# LC_BigOne_-_5_3A_MOSFET_for_TLC5940_2.net
KiCad netlist of a schematic drawn in Altium Designer
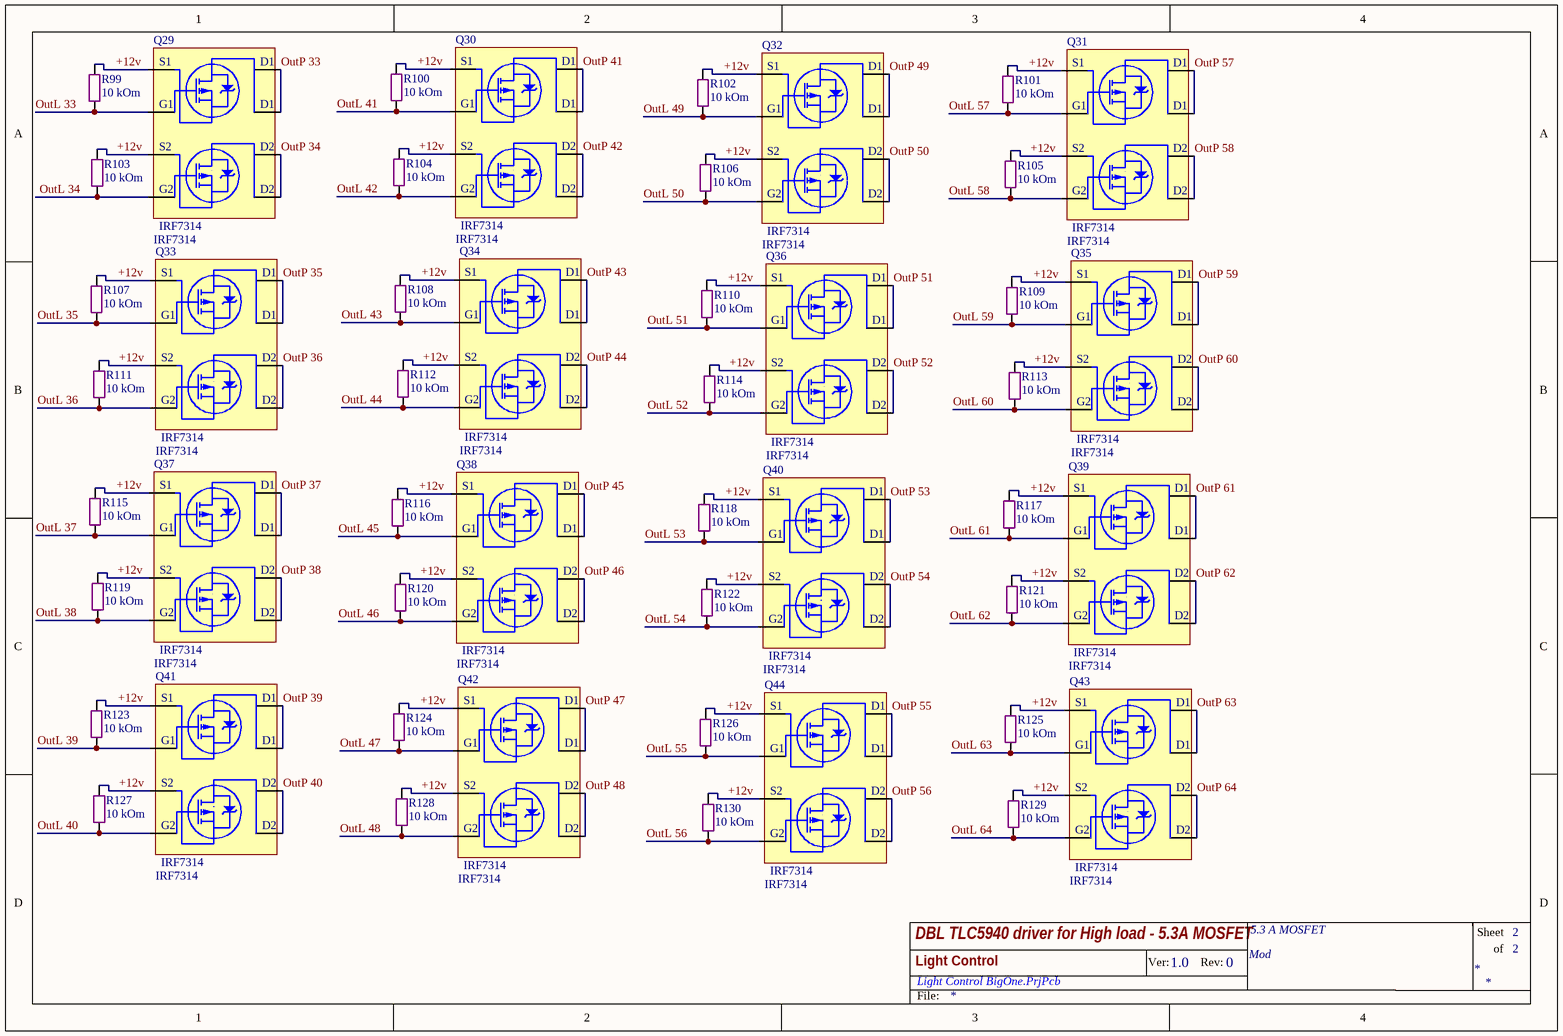
[diagram p0: LC BigOne - 5.3A MOSFET for TLC5940 2.SchDoc]

(export (version "E")
  (design (tool "Eeschema 10.0.6"))
  (components
    (comp (ref "Q29")
      (value "IRF7314")
      (footprint "GeneralCases:SO8")
      (description "Dual P-Ch  20V - 0.058Ω - 5.3A")
      (libsource (lib "Transistor") (part "IRF7314"))
    )
    (comp (ref "Q30")
      (value "IRF7314")
      (footprint "GeneralCases:SO8")
      (description "Dual P-Ch  20V - 0.058Ω - 5.3A")
      (libsource (lib "Transistor") (part "IRF7314"))
    )
    (comp (ref "Q31")
      (value "IRF7314")
      (footprint "GeneralCases:SO8")
      (description "Dual P-Ch  20V - 0.058Ω - 5.3A")
      (libsource (lib "Transistor") (part "IRF7314"))
    )
    (comp (ref "Q32")
      (value "IRF7314")
      (footprint "GeneralCases:SO8")
      (description "Dual P-Ch  20V - 0.058Ω - 5.3A")
      (libsource (lib "Transistor") (part "IRF7314"))
    )
    (comp (ref "Q33")
      (value "IRF7314")
      (footprint "GeneralCases:SO8")
      (description "Dual P-Ch  20V - 0.058Ω - 5.3A")
      (libsource (lib "Transistor") (part "IRF7314"))
    )
    (comp (ref "Q34")
      (value "IRF7314")
      (footprint "GeneralCases:SO8")
      (description "Dual P-Ch  20V - 0.058Ω - 5.3A")
      (libsource (lib "Transistor") (part "IRF7314"))
    )
    (comp (ref "Q35")
      (value "IRF7314")
      (footprint "GeneralCases:SO8")
      (description "Dual P-Ch  20V - 0.058Ω - 5.3A")
      (libsource (lib "Transistor") (part "IRF7314"))
    )
    (comp (ref "Q36")
      (value "IRF7314")
      (footprint "GeneralCases:SO8")
      (description "Dual P-Ch  20V - 0.058Ω - 5.3A")
      (libsource (lib "Transistor") (part "IRF7314"))
    )
    (comp (ref "Q37")
      (value "IRF7314")
      (footprint "GeneralCases:SO8")
      (description "Dual P-Ch  20V - 0.058Ω - 5.3A")
      (libsource (lib "Transistor") (part "IRF7314"))
    )
    (comp (ref "Q38")
      (value "IRF7314")
      (footprint "GeneralCases:SO8")
      (description "Dual P-Ch  20V - 0.058Ω - 5.3A")
      (libsource (lib "Transistor") (part "IRF7314"))
    )
    (comp (ref "Q39")
      (value "IRF7314")
      (footprint "GeneralCases:SO8")
      (description "Dual P-Ch  20V - 0.058Ω - 5.3A")
      (libsource (lib "Transistor") (part "IRF7314"))
    )
    (comp (ref "Q40")
      (value "IRF7314")
      (footprint "GeneralCases:SO8")
      (description "Dual P-Ch  20V - 0.058Ω - 5.3A")
      (libsource (lib "Transistor") (part "IRF7314"))
    )
    (comp (ref "Q41")
      (value "IRF7314")
      (footprint "GeneralCases:SO8")
      (description "Dual P-Ch  20V - 0.058Ω - 5.3A")
      (libsource (lib "Transistor") (part "IRF7314"))
    )
    (comp (ref "Q42")
      (value "IRF7314")
      (footprint "GeneralCases:SO8")
      (description "Dual P-Ch  20V - 0.058Ω - 5.3A")
      (libsource (lib "Transistor") (part "IRF7314"))
    )
    (comp (ref "Q43")
      (value "IRF7314")
      (footprint "GeneralCases:SO8")
      (description "Dual P-Ch  20V - 0.058Ω - 5.3A")
      (libsource (lib "Transistor") (part "IRF7314"))
    )
    (comp (ref "Q44")
      (value "IRF7314")
      (footprint "GeneralCases:SO8")
      (description "Dual P-Ch  20V - 0.058Ω - 5.3A")
      (libsource (lib "Transistor") (part "IRF7314"))
    )
    (comp (ref "R99")
      (value "10 kOm")
      (footprint "PassiveComponents:SMD 0805 (2012)")
      (libsource (lib "PassiveComponents") (part "Res All Types"))
    )
    (comp (ref "R100")
      (value "10 kOm")
      (footprint "PassiveComponents:SMD 0805 (2012)")
      (libsource (lib "PassiveComponents") (part "Res All Types"))
    )
    (comp (ref "R101")
      (value "10 kOm")
      (footprint "PassiveComponents:SMD 0805 (2012)")
      (libsource (lib "PassiveComponents") (part "Res All Types"))
    )
    (comp (ref "R102")
      (value "10 kOm")
      (footprint "PassiveComponents:SMD 0805 (2012)")
      (libsource (lib "PassiveComponents") (part "Res All Types"))
    )
    (comp (ref "R103")
      (value "10 kOm")
      (footprint "PassiveComponents:SMD 0805 (2012)")
      (libsource (lib "PassiveComponents") (part "Res All Types"))
    )
    (comp (ref "R104")
      (value "10 kOm")
      (footprint "PassiveComponents:SMD 0805 (2012)")
      (libsource (lib "PassiveComponents") (part "Res All Types"))
    )
    (comp (ref "R105")
      (value "10 kOm")
      (footprint "PassiveComponents:SMD 0805 (2012)")
      (libsource (lib "PassiveComponents") (part "Res All Types"))
    )
    (comp (ref "R106")
      (value "10 kOm")
      (footprint "PassiveComponents:SMD 0805 (2012)")
      (libsource (lib "PassiveComponents") (part "Res All Types"))
    )
    (comp (ref "R107")
      (value "10 kOm")
      (footprint "PassiveComponents:SMD 0805 (2012)")
      (libsource (lib "PassiveComponents") (part "Res All Types"))
    )
    (comp (ref "R108")
      (value "10 kOm")
      (footprint "PassiveComponents:SMD 0805 (2012)")
      (libsource (lib "PassiveComponents") (part "Res All Types"))
    )
    (comp (ref "R109")
      (value "10 kOm")
      (footprint "PassiveComponents:SMD 0805 (2012)")
      (libsource (lib "PassiveComponents") (part "Res All Types"))
    )
    (comp (ref "R110")
      (value "10 kOm")
      (footprint "PassiveComponents:SMD 0805 (2012)")
      (libsource (lib "PassiveComponents") (part "Res All Types"))
    )
    (comp (ref "R111")
      (value "10 kOm")
      (footprint "PassiveComponents:SMD 0805 (2012)")
      (libsource (lib "PassiveComponents") (part "Res All Types"))
    )
    (comp (ref "R112")
      (value "10 kOm")
      (footprint "PassiveComponents:SMD 0805 (2012)")
      (libsource (lib "PassiveComponents") (part "Res All Types"))
    )
    (comp (ref "R113")
      (value "10 kOm")
      (footprint "PassiveComponents:SMD 0805 (2012)")
      (libsource (lib "PassiveComponents") (part "Res All Types"))
    )
    (comp (ref "R114")
      (value "10 kOm")
      (footprint "PassiveComponents:SMD 0805 (2012)")
      (libsource (lib "PassiveComponents") (part "Res All Types"))
    )
    (comp (ref "R115")
      (value "10 kOm")
      (footprint "PassiveComponents:SMD 0805 (2012)")
      (libsource (lib "PassiveComponents") (part "Res All Types"))
    )
    (comp (ref "R116")
      (value "10 kOm")
      (footprint "PassiveComponents:SMD 0805 (2012)")
      (libsource (lib "PassiveComponents") (part "Res All Types"))
    )
    (comp (ref "R117")
      (value "10 kOm")
      (footprint "PassiveComponents:SMD 0805 (2012)")
      (libsource (lib "PassiveComponents") (part "Res All Types"))
    )
    (comp (ref "R118")
      (value "10 kOm")
      (footprint "PassiveComponents:SMD 0805 (2012)")
      (libsource (lib "PassiveComponents") (part "Res All Types"))
    )
    (comp (ref "R119")
      (value "10 kOm")
      (footprint "PassiveComponents:SMD 0805 (2012)")
      (libsource (lib "PassiveComponents") (part "Res All Types"))
    )
    (comp (ref "R120")
      (value "10 kOm")
      (footprint "PassiveComponents:SMD 0805 (2012)")
      (libsource (lib "PassiveComponents") (part "Res All Types"))
    )
    (comp (ref "R121")
      (value "10 kOm")
      (footprint "PassiveComponents:SMD 0805 (2012)")
      (libsource (lib "PassiveComponents") (part "Res All Types"))
    )
    (comp (ref "R122")
      (value "10 kOm")
      (footprint "PassiveComponents:SMD 0805 (2012)")
      (libsource (lib "PassiveComponents") (part "Res All Types"))
    )
    (comp (ref "R123")
      (value "10 kOm")
      (footprint "PassiveComponents:SMD 0805 (2012)")
      (libsource (lib "PassiveComponents") (part "Res All Types"))
    )
    (comp (ref "R124")
      (value "10 kOm")
      (footprint "PassiveComponents:SMD 0805 (2012)")
      (libsource (lib "PassiveComponents") (part "Res All Types"))
    )
    (comp (ref "R125")
      (value "10 kOm")
      (footprint "PassiveComponents:SMD 0805 (2012)")
      (libsource (lib "PassiveComponents") (part "Res All Types"))
    )
    (comp (ref "R126")
      (value "10 kOm")
      (footprint "PassiveComponents:SMD 0805 (2012)")
      (libsource (lib "PassiveComponents") (part "Res All Types"))
    )
    (comp (ref "R127")
      (value "10 kOm")
      (footprint "PassiveComponents:SMD 0805 (2012)")
      (libsource (lib "PassiveComponents") (part "Res All Types"))
    )
    (comp (ref "R128")
      (value "10 kOm")
      (footprint "PassiveComponents:SMD 0805 (2012)")
      (libsource (lib "PassiveComponents") (part "Res All Types"))
    )
    (comp (ref "R129")
      (value "10 kOm")
      (footprint "PassiveComponents:SMD 0805 (2012)")
      (libsource (lib "PassiveComponents") (part "Res All Types"))
    )
    (comp (ref "R130")
      (value "10 kOm")
      (footprint "PassiveComponents:SMD 0805 (2012)")
      (libsource (lib "PassiveComponents") (part "Res All Types"))
    )
  )
  (nets
    (net (code "1") (name "/+12v") (class "Default")
      (node (ref "Q29") (pin "1") (pinfunction "S_1") (pintype "passive"))
      (node (ref "Q29") (pin "3") (pinfunction "S_3") (pintype "passive"))
      (node (ref "Q30") (pin "1") (pinfunction "S_1") (pintype "passive"))
      (node (ref "Q30") (pin "3") (pinfunction "S_3") (pintype "passive"))
      (node (ref "Q31") (pin "1") (pinfunction "S_1") (pintype "passive"))
      (node (ref "Q31") (pin "3") (pinfunction "S_3") (pintype "passive"))
      (node (ref "Q32") (pin "1") (pinfunction "S_1") (pintype "passive"))
      (node (ref "Q32") (pin "3") (pinfunction "S_3") (pintype "passive"))
      (node (ref "Q33") (pin "1") (pinfunction "S_1") (pintype "passive"))
      (node (ref "Q33") (pin "3") (pinfunction "S_3") (pintype "passive"))
      (node (ref "Q34") (pin "1") (pinfunction "S_1") (pintype "passive"))
      (node (ref "Q34") (pin "3") (pinfunction "S_3") (pintype "passive"))
      (node (ref "Q35") (pin "1") (pinfunction "S_1") (pintype "passive"))
      (node (ref "Q35") (pin "3") (pinfunction "S_3") (pintype "passive"))
      (node (ref "Q36") (pin "1") (pinfunction "S_1") (pintype "passive"))
      (node (ref "Q36") (pin "3") (pinfunction "S_3") (pintype "passive"))
      (node (ref "Q37") (pin "1") (pinfunction "S_1") (pintype "passive"))
      (node (ref "Q37") (pin "3") (pinfunction "S_3") (pintype "passive"))
      (node (ref "Q38") (pin "1") (pinfunction "S_1") (pintype "passive"))
      (node (ref "Q38") (pin "3") (pinfunction "S_3") (pintype "passive"))
      (node (ref "Q39") (pin "1") (pinfunction "S_1") (pintype "passive"))
      (node (ref "Q39") (pin "3") (pinfunction "S_3") (pintype "passive"))
      (node (ref "Q40") (pin "1") (pinfunction "S_1") (pintype "passive"))
      (node (ref "Q40") (pin "3") (pinfunction "S_3") (pintype "passive"))
      (node (ref "Q41") (pin "1") (pinfunction "S_1") (pintype "passive"))
      (node (ref "Q41") (pin "3") (pinfunction "S_3") (pintype "passive"))
      (node (ref "Q42") (pin "1") (pinfunction "S_1") (pintype "passive"))
      (node (ref "Q42") (pin "3") (pinfunction "S_3") (pintype "passive"))
      (node (ref "Q43") (pin "1") (pinfunction "S_1") (pintype "passive"))
      (node (ref "Q43") (pin "3") (pinfunction "S_3") (pintype "passive"))
      (node (ref "Q44") (pin "1") (pinfunction "S_1") (pintype "passive"))
      (node (ref "Q44") (pin "3") (pinfunction "S_3") (pintype "passive"))
      (node (ref "R100") (pin "2") (pinfunction "2_2") (pintype "passive"))
      (node (ref "R101") (pin "2") (pinfunction "2_2") (pintype "passive"))
      (node (ref "R102") (pin "2") (pinfunction "2_2") (pintype "passive"))
      (node (ref "R103") (pin "2") (pinfunction "2_2") (pintype "passive"))
      (node (ref "R104") (pin "2") (pinfunction "2_2") (pintype "passive"))
      (node (ref "R105") (pin "2") (pinfunction "2_2") (pintype "passive"))
      (node (ref "R106") (pin "2") (pinfunction "2_2") (pintype "passive"))
      (node (ref "R107") (pin "2") (pinfunction "2_2") (pintype "passive"))
      (node (ref "R108") (pin "2") (pinfunction "2_2") (pintype "passive"))
      (node (ref "R109") (pin "2") (pinfunction "2_2") (pintype "passive"))
      (node (ref "R110") (pin "2") (pinfunction "2_2") (pintype "passive"))
      (node (ref "R111") (pin "2") (pinfunction "2_2") (pintype "passive"))
      (node (ref "R112") (pin "2") (pinfunction "2_2") (pintype "passive"))
      (node (ref "R113") (pin "2") (pinfunction "2_2") (pintype "passive"))
      (node (ref "R114") (pin "2") (pinfunction "2_2") (pintype "passive"))
      (node (ref "R115") (pin "2") (pinfunction "2_2") (pintype "passive"))
      (node (ref "R116") (pin "2") (pinfunction "2_2") (pintype "passive"))
      (node (ref "R117") (pin "2") (pinfunction "2_2") (pintype "passive"))
      (node (ref "R118") (pin "2") (pinfunction "2_2") (pintype "passive"))
      (node (ref "R119") (pin "2") (pinfunction "2_2") (pintype "passive"))
      (node (ref "R120") (pin "2") (pinfunction "2_2") (pintype "passive"))
      (node (ref "R121") (pin "2") (pinfunction "2_2") (pintype "passive"))
      (node (ref "R122") (pin "2") (pinfunction "2_2") (pintype "passive"))
      (node (ref "R123") (pin "2") (pinfunction "2_2") (pintype "passive"))
      (node (ref "R124") (pin "2") (pinfunction "2_2") (pintype "passive"))
      (node (ref "R125") (pin "2") (pinfunction "2_2") (pintype "passive"))
      (node (ref "R126") (pin "2") (pinfunction "2_2") (pintype "passive"))
      (node (ref "R127") (pin "2") (pinfunction "2_2") (pintype "passive"))
      (node (ref "R128") (pin "2") (pinfunction "2_2") (pintype "passive"))
      (node (ref "R129") (pin "2") (pinfunction "2_2") (pintype "passive"))
      (node (ref "R130") (pin "2") (pinfunction "2_2") (pintype "passive"))
      (node (ref "R99") (pin "2") (pinfunction "2_2") (pintype "passive"))
    )
    (net (code "2") (name "/OutL 33") (class "Default")
      (node (ref "Q29") (pin "2") (pinfunction "G_2") (pintype "passive"))
      (node (ref "R99") (pin "1") (pinfunction "1_1") (pintype "passive"))
    )
    (net (code "3") (name "/OutL 34") (class "Default")
      (node (ref "Q29") (pin "4") (pinfunction "G_4") (pintype "passive"))
      (node (ref "R103") (pin "1") (pinfunction "1_1") (pintype "passive"))
    )
    (net (code "4") (name "/OutL 35") (class "Default")
      (node (ref "Q33") (pin "2") (pinfunction "G_2") (pintype "passive"))
      (node (ref "R107") (pin "1") (pinfunction "1_1") (pintype "passive"))
    )
    (net (code "5") (name "/OutL 36") (class "Default")
      (node (ref "Q33") (pin "4") (pinfunction "G_4") (pintype "passive"))
      (node (ref "R111") (pin "1") (pinfunction "1_1") (pintype "passive"))
    )
    (net (code "6") (name "/OutL 37") (class "Default")
      (node (ref "Q37") (pin "2") (pinfunction "G_2") (pintype "passive"))
      (node (ref "R115") (pin "1") (pinfunction "1_1") (pintype "passive"))
    )
    (net (code "7") (name "/OutL 38") (class "Default")
      (node (ref "Q37") (pin "4") (pinfunction "G_4") (pintype "passive"))
      (node (ref "R119") (pin "1") (pinfunction "1_1") (pintype "passive"))
    )
    (net (code "8") (name "/OutL 39") (class "Default")
      (node (ref "Q41") (pin "2") (pinfunction "G_2") (pintype "passive"))
      (node (ref "R123") (pin "1") (pinfunction "1_1") (pintype "passive"))
    )
    (net (code "9") (name "/OutL 40") (class "Default")
      (node (ref "Q41") (pin "4") (pinfunction "G_4") (pintype "passive"))
      (node (ref "R127") (pin "1") (pinfunction "1_1") (pintype "passive"))
    )
    (net (code "10") (name "/OutL 41") (class "Default")
      (node (ref "Q30") (pin "2") (pinfunction "G_2") (pintype "passive"))
      (node (ref "R100") (pin "1") (pinfunction "1_1") (pintype "passive"))
    )
    (net (code "11") (name "/OutL 42") (class "Default")
      (node (ref "Q30") (pin "4") (pinfunction "G_4") (pintype "passive"))
      (node (ref "R104") (pin "1") (pinfunction "1_1") (pintype "passive"))
    )
    (net (code "12") (name "/OutL 43") (class "Default")
      (node (ref "Q34") (pin "2") (pinfunction "G_2") (pintype "passive"))
      (node (ref "R108") (pin "1") (pinfunction "1_1") (pintype "passive"))
    )
    (net (code "13") (name "/OutL 44") (class "Default")
      (node (ref "Q34") (pin "4") (pinfunction "G_4") (pintype "passive"))
      (node (ref "R112") (pin "1") (pinfunction "1_1") (pintype "passive"))
    )
    (net (code "14") (name "/OutL 45") (class "Default")
      (node (ref "Q38") (pin "2") (pinfunction "G_2") (pintype "passive"))
      (node (ref "R116") (pin "1") (pinfunction "1_1") (pintype "passive"))
    )
    (net (code "15") (name "/OutL 46") (class "Default")
      (node (ref "Q38") (pin "4") (pinfunction "G_4") (pintype "passive"))
      (node (ref "R120") (pin "1") (pinfunction "1_1") (pintype "passive"))
    )
    (net (code "16") (name "/OutL 47") (class "Default")
      (node (ref "Q42") (pin "2") (pinfunction "G_2") (pintype "passive"))
      (node (ref "R124") (pin "1") (pinfunction "1_1") (pintype "passive"))
    )
    (net (code "17") (name "/OutL 48") (class "Default")
      (node (ref "Q42") (pin "4") (pinfunction "G_4") (pintype "passive"))
      (node (ref "R128") (pin "1") (pinfunction "1_1") (pintype "passive"))
    )
    (net (code "18") (name "/OutL 49") (class "Default")
      (node (ref "Q32") (pin "2") (pinfunction "G_2") (pintype "passive"))
      (node (ref "R102") (pin "1") (pinfunction "1_1") (pintype "passive"))
    )
    (net (code "19") (name "/OutL 50") (class "Default")
      (node (ref "Q32") (pin "4") (pinfunction "G_4") (pintype "passive"))
      (node (ref "R106") (pin "1") (pinfunction "1_1") (pintype "passive"))
    )
    (net (code "20") (name "/OutL 51") (class "Default")
      (node (ref "Q36") (pin "2") (pinfunction "G_2") (pintype "passive"))
      (node (ref "R110") (pin "1") (pinfunction "1_1") (pintype "passive"))
    )
    (net (code "21") (name "/OutL 52") (class "Default")
      (node (ref "Q36") (pin "4") (pinfunction "G_4") (pintype "passive"))
      (node (ref "R114") (pin "1") (pinfunction "1_1") (pintype "passive"))
    )
    (net (code "22") (name "/OutL 53") (class "Default")
      (node (ref "Q40") (pin "2") (pinfunction "G_2") (pintype "passive"))
      (node (ref "R118") (pin "1") (pinfunction "1_1") (pintype "passive"))
    )
    (net (code "23") (name "/OutL 54") (class "Default")
      (node (ref "Q40") (pin "4") (pinfunction "G_4") (pintype "passive"))
      (node (ref "R122") (pin "1") (pinfunction "1_1") (pintype "passive"))
    )
    (net (code "24") (name "/OutL 55") (class "Default")
      (node (ref "Q44") (pin "2") (pinfunction "G_2") (pintype "passive"))
      (node (ref "R126") (pin "1") (pinfunction "1_1") (pintype "passive"))
    )
    (net (code "25") (name "/OutL 56") (class "Default")
      (node (ref "Q44") (pin "4") (pinfunction "G_4") (pintype "passive"))
      (node (ref "R130") (pin "1") (pinfunction "1_1") (pintype "passive"))
    )
    (net (code "26") (name "/OutL 57") (class "Default")
      (node (ref "Q31") (pin "2") (pinfunction "G_2") (pintype "passive"))
      (node (ref "R101") (pin "1") (pinfunction "1_1") (pintype "passive"))
    )
    (net (code "27") (name "/OutL 58") (class "Default")
      (node (ref "Q31") (pin "4") (pinfunction "G_4") (pintype "passive"))
      (node (ref "R105") (pin "1") (pinfunction "1_1") (pintype "passive"))
    )
    (net (code "28") (name "/OutL 59") (class "Default")
      (node (ref "Q35") (pin "2") (pinfunction "G_2") (pintype "passive"))
      (node (ref "R109") (pin "1") (pinfunction "1_1") (pintype "passive"))
    )
    (net (code "29") (name "/OutL 60") (class "Default")
      (node (ref "Q35") (pin "4") (pinfunction "G_4") (pintype "passive"))
      (node (ref "R113") (pin "1") (pinfunction "1_1") (pintype "passive"))
    )
    (net (code "30") (name "/OutL 61") (class "Default")
      (node (ref "Q39") (pin "2") (pinfunction "G_2") (pintype "passive"))
      (node (ref "R117") (pin "1") (pinfunction "1_1") (pintype "passive"))
    )
    (net (code "31") (name "/OutL 62") (class "Default")
      (node (ref "Q39") (pin "4") (pinfunction "G_4") (pintype "passive"))
      (node (ref "R121") (pin "1") (pinfunction "1_1") (pintype "passive"))
    )
    (net (code "32") (name "/OutL 63") (class "Default")
      (node (ref "Q43") (pin "2") (pinfunction "G_2") (pintype "passive"))
      (node (ref "R125") (pin "1") (pinfunction "1_1") (pintype "passive"))
    )
    (net (code "33") (name "/OutL 64") (class "Default")
      (node (ref "Q43") (pin "4") (pinfunction "G_4") (pintype "passive"))
      (node (ref "R129") (pin "1") (pinfunction "1_1") (pintype "passive"))
    )
    (net (code "34") (name "/OutP 33") (class "Default")
      (node (ref "Q29") (pin "7") (pinfunction "D_7") (pintype "passive"))
      (node (ref "Q29") (pin "8") (pinfunction "D_8") (pintype "passive"))
    )
    (net (code "35") (name "/OutP 34") (class "Default")
      (node (ref "Q29") (pin "5") (pinfunction "D_5") (pintype "passive"))
      (node (ref "Q29") (pin "6") (pinfunction "D_6") (pintype "passive"))
    )
    (net (code "36") (name "/OutP 35") (class "Default")
      (node (ref "Q33") (pin "7") (pinfunction "D_7") (pintype "passive"))
      (node (ref "Q33") (pin "8") (pinfunction "D_8") (pintype "passive"))
    )
    (net (code "37") (name "/OutP 36") (class "Default")
      (node (ref "Q33") (pin "5") (pinfunction "D_5") (pintype "passive"))
      (node (ref "Q33") (pin "6") (pinfunction "D_6") (pintype "passive"))
    )
    (net (code "38") (name "/OutP 37") (class "Default")
      (node (ref "Q37") (pin "7") (pinfunction "D_7") (pintype "passive"))
      (node (ref "Q37") (pin "8") (pinfunction "D_8") (pintype "passive"))
    )
    (net (code "39") (name "/OutP 38") (class "Default")
      (node (ref "Q37") (pin "5") (pinfunction "D_5") (pintype "passive"))
      (node (ref "Q37") (pin "6") (pinfunction "D_6") (pintype "passive"))
    )
    (net (code "40") (name "/OutP 39") (class "Default")
      (node (ref "Q41") (pin "7") (pinfunction "D_7") (pintype "passive"))
      (node (ref "Q41") (pin "8") (pinfunction "D_8") (pintype "passive"))
    )
    (net (code "41") (name "/OutP 40") (class "Default")
      (node (ref "Q41") (pin "5") (pinfunction "D_5") (pintype "passive"))
      (node (ref "Q41") (pin "6") (pinfunction "D_6") (pintype "passive"))
    )
    (net (code "42") (name "/OutP 41") (class "Default")
      (node (ref "Q30") (pin "7") (pinfunction "D_7") (pintype "passive"))
      (node (ref "Q30") (pin "8") (pinfunction "D_8") (pintype "passive"))
    )
    (net (code "43") (name "/OutP 42") (class "Default")
      (node (ref "Q30") (pin "5") (pinfunction "D_5") (pintype "passive"))
      (node (ref "Q30") (pin "6") (pinfunction "D_6") (pintype "passive"))
    )
    (net (code "44") (name "/OutP 43") (class "Default")
      (node (ref "Q34") (pin "7") (pinfunction "D_7") (pintype "passive"))
      (node (ref "Q34") (pin "8") (pinfunction "D_8") (pintype "passive"))
    )
    (net (code "45") (name "/OutP 44") (class "Default")
      (node (ref "Q34") (pin "5") (pinfunction "D_5") (pintype "passive"))
      (node (ref "Q34") (pin "6") (pinfunction "D_6") (pintype "passive"))
    )
    (net (code "46") (name "/OutP 45") (class "Default")
      (node (ref "Q38") (pin "7") (pinfunction "D_7") (pintype "passive"))
      (node (ref "Q38") (pin "8") (pinfunction "D_8") (pintype "passive"))
    )
    (net (code "47") (name "/OutP 46") (class "Default")
      (node (ref "Q38") (pin "5") (pinfunction "D_5") (pintype "passive"))
      (node (ref "Q38") (pin "6") (pinfunction "D_6") (pintype "passive"))
    )
    (net (code "48") (name "/OutP 47") (class "Default")
      (node (ref "Q42") (pin "7") (pinfunction "D_7") (pintype "passive"))
      (node (ref "Q42") (pin "8") (pinfunction "D_8") (pintype "passive"))
    )
    (net (code "49") (name "/OutP 48") (class "Default")
      (node (ref "Q42") (pin "5") (pinfunction "D_5") (pintype "passive"))
      (node (ref "Q42") (pin "6") (pinfunction "D_6") (pintype "passive"))
    )
    (net (code "50") (name "/OutP 49") (class "Default")
      (node (ref "Q32") (pin "7") (pinfunction "D_7") (pintype "passive"))
      (node (ref "Q32") (pin "8") (pinfunction "D_8") (pintype "passive"))
    )
    (net (code "51") (name "/OutP 50") (class "Default")
      (node (ref "Q32") (pin "5") (pinfunction "D_5") (pintype "passive"))
      (node (ref "Q32") (pin "6") (pinfunction "D_6") (pintype "passive"))
    )
    (net (code "52") (name "/OutP 51") (class "Default")
      (node (ref "Q36") (pin "7") (pinfunction "D_7") (pintype "passive"))
      (node (ref "Q36") (pin "8") (pinfunction "D_8") (pintype "passive"))
    )
    (net (code "53") (name "/OutP 52") (class "Default")
      (node (ref "Q36") (pin "5") (pinfunction "D_5") (pintype "passive"))
      (node (ref "Q36") (pin "6") (pinfunction "D_6") (pintype "passive"))
    )
    (net (code "54") (name "/OutP 53") (class "Default")
      (node (ref "Q40") (pin "7") (pinfunction "D_7") (pintype "passive"))
      (node (ref "Q40") (pin "8") (pinfunction "D_8") (pintype "passive"))
    )
    (net (code "55") (name "/OutP 54") (class "Default")
      (node (ref "Q40") (pin "5") (pinfunction "D_5") (pintype "passive"))
      (node (ref "Q40") (pin "6") (pinfunction "D_6") (pintype "passive"))
    )
    (net (code "56") (name "/OutP 55") (class "Default")
      (node (ref "Q44") (pin "7") (pinfunction "D_7") (pintype "passive"))
      (node (ref "Q44") (pin "8") (pinfunction "D_8") (pintype "passive"))
    )
    (net (code "57") (name "/OutP 56") (class "Default")
      (node (ref "Q44") (pin "5") (pinfunction "D_5") (pintype "passive"))
      (node (ref "Q44") (pin "6") (pinfunction "D_6") (pintype "passive"))
    )
    (net (code "58") (name "/OutP 57") (class "Default")
      (node (ref "Q31") (pin "7") (pinfunction "D_7") (pintype "passive"))
      (node (ref "Q31") (pin "8") (pinfunction "D_8") (pintype "passive"))
    )
    (net (code "59") (name "/OutP 58") (class "Default")
      (node (ref "Q31") (pin "5") (pinfunction "D_5") (pintype "passive"))
      (node (ref "Q31") (pin "6") (pinfunction "D_6") (pintype "passive"))
    )
    (net (code "60") (name "/OutP 59") (class "Default")
      (node (ref "Q35") (pin "7") (pinfunction "D_7") (pintype "passive"))
      (node (ref "Q35") (pin "8") (pinfunction "D_8") (pintype "passive"))
    )
    (net (code "61") (name "/OutP 60") (class "Default")
      (node (ref "Q35") (pin "5") (pinfunction "D_5") (pintype "passive"))
      (node (ref "Q35") (pin "6") (pinfunction "D_6") (pintype "passive"))
    )
    (net (code "62") (name "/OutP 61") (class "Default")
      (node (ref "Q39") (pin "7") (pinfunction "D_7") (pintype "passive"))
      (node (ref "Q39") (pin "8") (pinfunction "D_8") (pintype "passive"))
    )
    (net (code "63") (name "/OutP 62") (class "Default")
      (node (ref "Q39") (pin "5") (pinfunction "D_5") (pintype "passive"))
      (node (ref "Q39") (pin "6") (pinfunction "D_6") (pintype "passive"))
    )
    (net (code "64") (name "/OutP 63") (class "Default")
      (node (ref "Q43") (pin "7") (pinfunction "D_7") (pintype "passive"))
      (node (ref "Q43") (pin "8") (pinfunction "D_8") (pintype "passive"))
    )
    (net (code "65") (name "/OutP 64") (class "Default")
      (node (ref "Q43") (pin "5") (pinfunction "D_5") (pintype "passive"))
      (node (ref "Q43") (pin "6") (pinfunction "D_6") (pintype "passive"))
    )
  )
)
